# SuniderPra.net
KiCad netlist of a schematic drawn in EAGLE
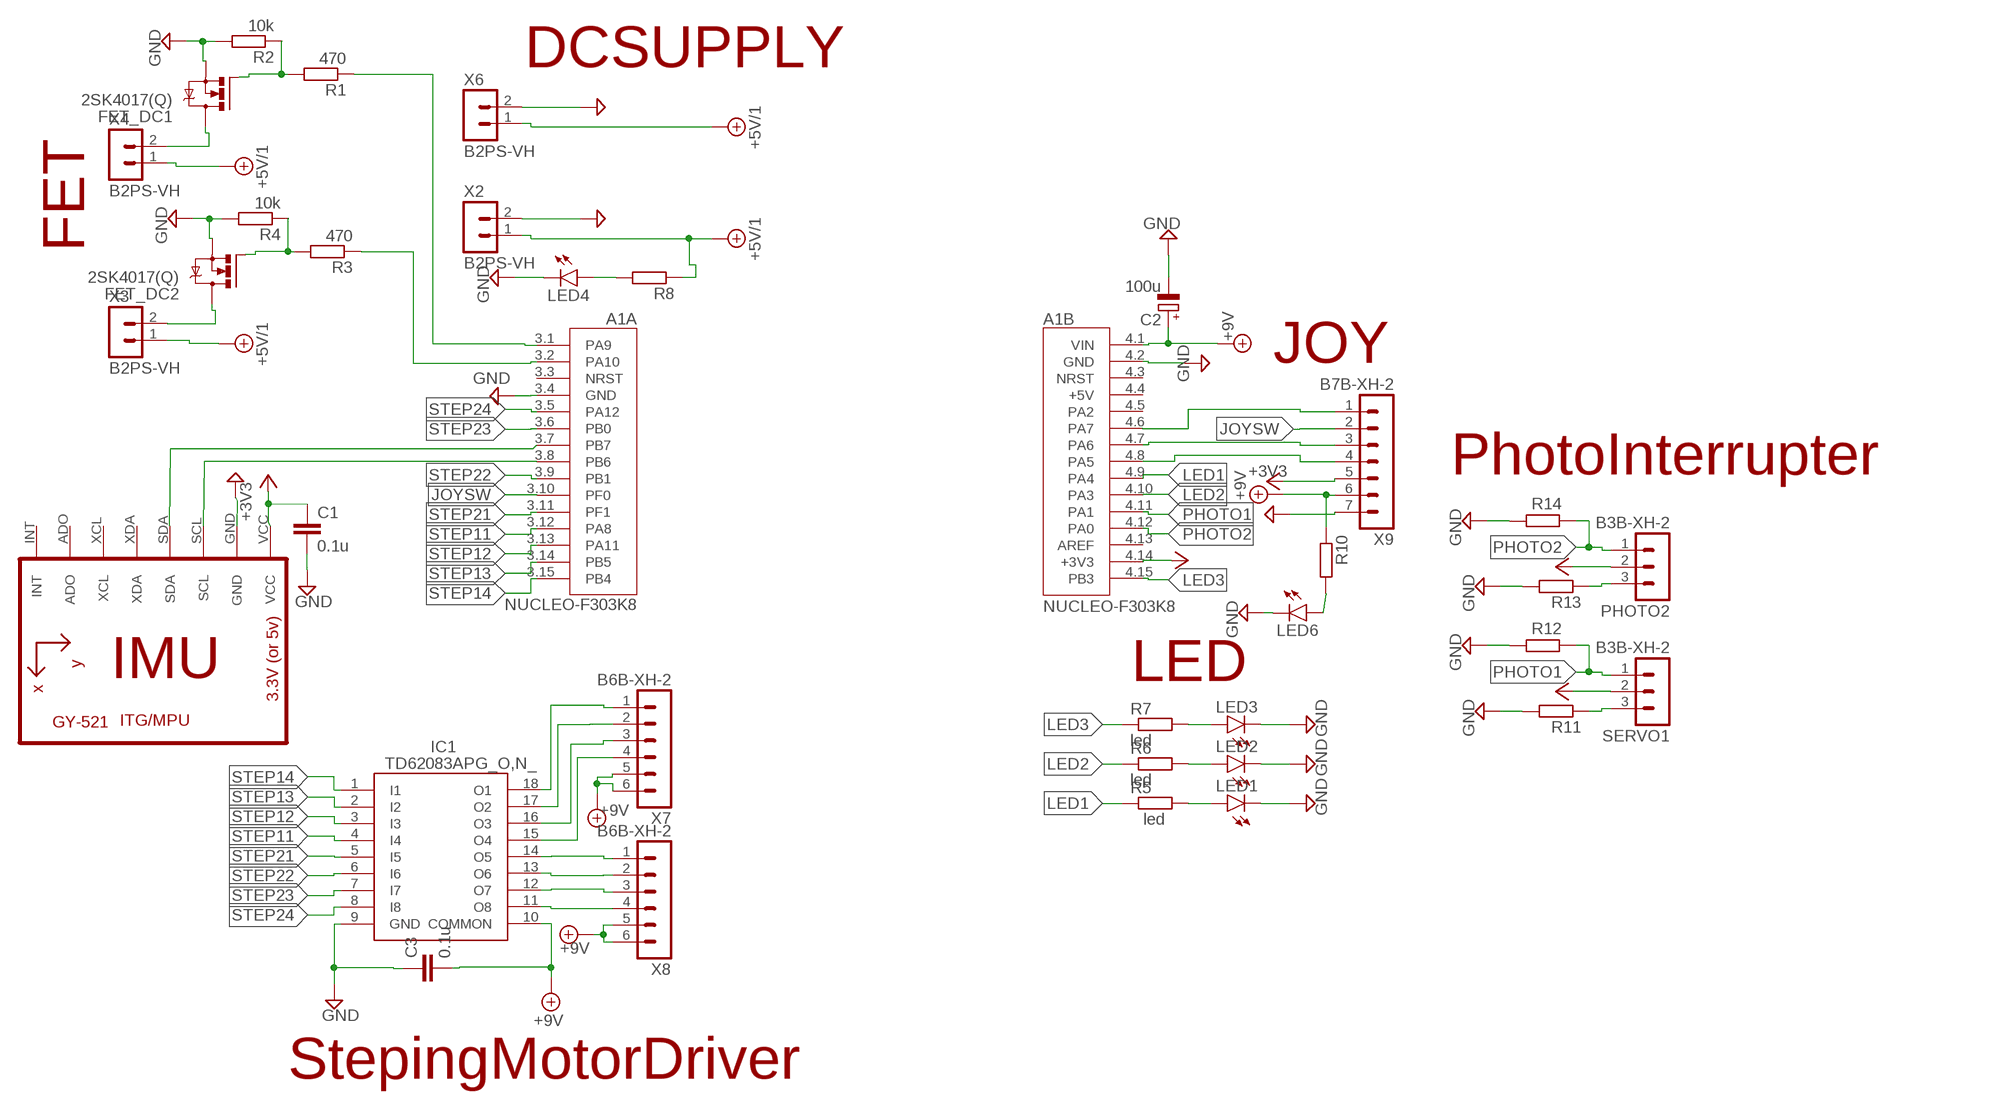
[diagram p0: schematic, sheet 1]

(export (version "E")
  (design (tool "Eeschema 10.0.6"))
  (components
    (comp (ref "A1")
      (value "NUCLEO-F303K8")
      (footprint "eagle-import:MODULE_NUCLEO-F303K8")
      (fields (field (name "MF") "STMicroelectronics"))
      (libsource (lib "eagle-import") (part "NUCLEO-F303K8"))
    )
    (comp (ref "C1")
      (value "0.1u")
      (footprint "eagle-import:C050-024X044")
      (libsource (lib "eagle-import") (part "C-EU050-024X044"))
    )
    (comp (ref "C2")
      (value "100u")
      (footprint "eagle-import:E2,5-6E")
      (libsource (lib "eagle-import") (part "CPOL-EUE2,5-6E"))
    )
    (comp (ref "C3")
      (value "0.1u")
      (footprint "eagle-import:C050-024X044")
      (libsource (lib "eagle-import") (part "C-EU050-024X044"))
    )
    (comp (ref "FET_DC1")
      (value "2SK4017(Q)")
      (footprint "eagle-import:TO230P230X650X740-3P")
      (fields (field (name "MF") "Toshiba Semiconductor"))
      (libsource (lib "eagle-import") (part "2SK4017(Q)"))
    )
    (comp (ref "FET_DC2")
      (value "2SK4017(Q)")
      (footprint "eagle-import:TO230P230X650X740-3P")
      (fields (field (name "MF") "Toshiba Semiconductor"))
      (libsource (lib "eagle-import") (part "2SK4017(Q)"))
    )
    (comp (ref "IC1")
      (value "TD62083APG_O,N_")
      (footprint "eagle-import:DIP762W60P254L2510H445Q18N")
      (fields
        (field (name "MANUFACTURER_PART_NUMBER") "TD62083APG(O,N)")
        (field (name "MOUSER_PART_NUMBER") "757-TD62083APGON")
      )
      (libsource (lib "eagle-import") (part "TD62083APG_O,N_"))
    )
    (comp (ref "IMU")
      (value "GY-521MPU6050")
      (footprint "eagle-import:GY-521")
      (libsource (lib "eagle-import") (part "GY-521MPU6050"))
    )
    (comp (ref "LED1")
      (value "LED3MM")
      (footprint "eagle-import:LED3MM")
      (libsource (lib "eagle-import") (part "LED3MM"))
    )
    (comp (ref "LED2")
      (value "LED3MM")
      (footprint "eagle-import:LED3MM")
      (libsource (lib "eagle-import") (part "LED3MM"))
    )
    (comp (ref "LED3")
      (value "LED3MM")
      (footprint "eagle-import:LED3MM")
      (libsource (lib "eagle-import") (part "LED3MM"))
    )
    (comp (ref "LED4")
      (value "LED3MM")
      (footprint "eagle-import:LED3MM")
      (libsource (lib "eagle-import") (part "LED3MM"))
    )
    (comp (ref "LED6")
      (value "LED3MM")
      (footprint "eagle-import:LED3MM")
      (libsource (lib "eagle-import") (part "LED3MM"))
    )
    (comp (ref "PHOTO2")
      (value "B3B-XH-2")
      (footprint "eagle-import:B3B-XH-A")
      (libsource (lib "eagle-import") (part "B3B-XH-2"))
    )
    (comp (ref "R1")
      (value "470")
      (footprint "eagle-import:0207_7")
      (libsource (lib "eagle-import") (part "R-EU_0207/7"))
    )
    (comp (ref "R2")
      (value "10k")
      (footprint "eagle-import:0207_7")
      (libsource (lib "eagle-import") (part "R-EU_0207/7"))
    )
    (comp (ref "R3")
      (value "470")
      (footprint "eagle-import:0207_7")
      (libsource (lib "eagle-import") (part "R-EU_0207/7"))
    )
    (comp (ref "R4")
      (value "10k")
      (footprint "eagle-import:0207_7")
      (libsource (lib "eagle-import") (part "R-EU_0207/7"))
    )
    (comp (ref "R5")
      (value "led")
      (footprint "eagle-import:0207_7")
      (libsource (lib "eagle-import") (part "R-EU_0207/7"))
    )
    (comp (ref "R6")
      (value "led")
      (footprint "eagle-import:0207_7")
      (libsource (lib "eagle-import") (part "R-EU_0207/7"))
    )
    (comp (ref "R7")
      (value "led")
      (footprint "eagle-import:0207_7")
      (libsource (lib "eagle-import") (part "R-EU_0207/7"))
    )
    (comp (ref "R8")
      (value "led")
      (footprint "eagle-import:0207_7")
      (libsource (lib "eagle-import") (part "R-EU_0207/7"))
    )
    (comp (ref "R10")
      (value "led")
      (footprint "eagle-import:0207_7")
      (libsource (lib "eagle-import") (part "R-EU_0207/7"))
    )
    (comp (ref "R11")
      (value "220")
      (footprint "eagle-import:0207_7")
      (libsource (lib "eagle-import") (part "R-EU_0207/7"))
    )
    (comp (ref "R12")
      (value "10k")
      (footprint "eagle-import:0207_7")
      (libsource (lib "eagle-import") (part "R-EU_0207/7"))
    )
    (comp (ref "R13")
      (value "220")
      (footprint "eagle-import:0207_7")
      (libsource (lib "eagle-import") (part "R-EU_0207/7"))
    )
    (comp (ref "R14")
      (value "10k")
      (footprint "eagle-import:0207_7")
      (libsource (lib "eagle-import") (part "R-EU_0207/7"))
    )
    (comp (ref "SERVO1")
      (value "B3B-XH-2")
      (footprint "eagle-import:B3B-XH-A")
      (libsource (lib "eagle-import") (part "B3B-XH-2"))
    )
    (comp (ref "X2")
      (value "B2PS-VH")
      (footprint "eagle-import:B2PS-VH")
      (libsource (lib "eagle-import") (part "B2PS-VH"))
    )
    (comp (ref "X3")
      (value "B2PS-VH")
      (footprint "eagle-import:B2PS-VH")
      (libsource (lib "eagle-import") (part "B2PS-VH"))
    )
    (comp (ref "X4")
      (value "B2PS-VH")
      (footprint "eagle-import:B2PS-VH")
      (libsource (lib "eagle-import") (part "B2PS-VH"))
    )
    (comp (ref "X6")
      (value "B2PS-VH")
      (footprint "eagle-import:B2PS-VH")
      (libsource (lib "eagle-import") (part "B2PS-VH"))
    )
    (comp (ref "X7")
      (value "B6B-XH-2")
      (footprint "eagle-import:B6B-XH-A")
      (libsource (lib "eagle-import") (part "B6B-XH-2"))
    )
    (comp (ref "X8")
      (value "B6B-XH-2")
      (footprint "eagle-import:B6B-XH-A")
      (libsource (lib "eagle-import") (part "B6B-XH-2"))
    )
    (comp (ref "X9")
      (value "B7B-XH-2")
      (footprint "eagle-import:B7B-XH-A")
      (libsource (lib "eagle-import") (part "B7B-XH-2"))
    )
  )
  (nets
    (net (code "1") (name "+3V3") (class "Default")
      (node (ref "A1") (pin "4.14") (pinfunction "+3V3_4.14") (pintype "bidirectional"))
      (node (ref "C1") (pin "1") (pinfunction "1_1") (pintype "passive"))
      (node (ref "IMU") (pin "VCC") (pinfunction "VCC_VCC") (pintype "bidirectional"))
      (node (ref "PHOTO2") (pin "2") (pinfunction "2_2") (pintype "passive"))
      (node (ref "SERVO1") (pin "2") (pinfunction "2_2") (pintype "passive"))
      (node (ref "X9") (pin "5") (pinfunction "5_5") (pintype "passive"))
    )
    (net (code "2") (name "+5V{slash}1") (class "Default")
      (node (ref "R8") (pin "1") (pinfunction "1_1") (pintype "passive"))
      (node (ref "X2") (pin "1") (pinfunction "1_1") (pintype "passive"))
      (node (ref "X3") (pin "1") (pinfunction "1_1") (pintype "passive"))
      (node (ref "X4") (pin "1") (pinfunction "1_1") (pintype "passive"))
      (node (ref "X6") (pin "1") (pinfunction "1_1") (pintype "passive"))
    )
    (net (code "3") (name "+9V") (class "Default")
      (node (ref "A1") (pin "4.1") (pinfunction "VIN_4.1") (pintype "bidirectional"))
      (node (ref "C2") (pin "+") (pinfunction "+_+") (pintype "passive"))
      (node (ref "C3") (pin "2") (pinfunction "2_2") (pintype "passive"))
      (node (ref "IC1") (pin "10") (pinfunction "COMMON_10") (pintype "bidirectional"))
      (node (ref "R10") (pin "1") (pinfunction "1_1") (pintype "passive"))
      (node (ref "X7") (pin "5") (pinfunction "5_5") (pintype "passive"))
      (node (ref "X7") (pin "6") (pinfunction "6_6") (pintype "passive"))
      (node (ref "X8") (pin "5") (pinfunction "5_5") (pintype "passive"))
      (node (ref "X8") (pin "6") (pinfunction "6_6") (pintype "passive"))
      (node (ref "X9") (pin "6") (pinfunction "6_6") (pintype "passive"))
    )
    (net (code "4") (name "GND") (class "Default")
      (node (ref "A1") (pin "3.4") (pinfunction "GND_3.4") (pintype "bidirectional"))
      (node (ref "A1") (pin "4.2") (pinfunction "GND_4.2") (pintype "bidirectional"))
      (node (ref "C1") (pin "2") (pinfunction "2_2") (pintype "passive"))
      (node (ref "C2") (pin "-") (pinfunction "-_-") (pintype "passive"))
      (node (ref "C3") (pin "1") (pinfunction "1_1") (pintype "passive"))
      (node (ref "FET_DC1") (pin "3") (pinfunction "S_3") (pintype "passive"))
      (node (ref "FET_DC2") (pin "3") (pinfunction "S_3") (pintype "passive"))
      (node (ref "IC1") (pin "9") (pinfunction "GND_9") (pintype "bidirectional"))
      (node (ref "IMU") (pin "GND") (pinfunction "GND_GND") (pintype "bidirectional"))
      (node (ref "LED1") (pin "K") (pinfunction "C_K") (pintype "passive"))
      (node (ref "LED2") (pin "K") (pinfunction "C_K") (pintype "passive"))
      (node (ref "LED3") (pin "K") (pinfunction "C_K") (pintype "passive"))
      (node (ref "LED4") (pin "K") (pinfunction "C_K") (pintype "passive"))
      (node (ref "LED6") (pin "K") (pinfunction "C_K") (pintype "passive"))
      (node (ref "R11") (pin "2") (pinfunction "2_2") (pintype "passive"))
      (node (ref "R12") (pin "2") (pinfunction "2_2") (pintype "passive"))
      (node (ref "R13") (pin "2") (pinfunction "2_2") (pintype "passive"))
      (node (ref "R14") (pin "2") (pinfunction "2_2") (pintype "passive"))
      (node (ref "R2") (pin "2") (pinfunction "2_2") (pintype "passive"))
      (node (ref "R4") (pin "2") (pinfunction "2_2") (pintype "passive"))
      (node (ref "X2") (pin "2") (pinfunction "2_2") (pintype "passive"))
      (node (ref "X6") (pin "2") (pinfunction "2_2") (pintype "passive"))
      (node (ref "X9") (pin "7") (pinfunction "7_7") (pintype "passive"))
    )
    (net (code "5") (name "JOYSW") (class "Default")
      (node (ref "A1") (pin "3.10") (pinfunction "PF0_3.10") (pintype "bidirectional"))
      (node (ref "X9") (pin "2") (pinfunction "2_2") (pintype "passive"))
    )
    (net (code "6") (name "LED1") (class "Default")
      (node (ref "A1") (pin "4.9") (pinfunction "PA4_4.9") (pintype "bidirectional"))
      (node (ref "R5") (pin "1") (pinfunction "1_1") (pintype "passive"))
    )
    (net (code "7") (name "LED2") (class "Default")
      (node (ref "A1") (pin "4.10") (pinfunction "PA3_4.10") (pintype "bidirectional"))
      (node (ref "R6") (pin "1") (pinfunction "1_1") (pintype "passive"))
    )
    (net (code "8") (name "LED3") (class "Default")
      (node (ref "A1") (pin "4.15") (pinfunction "PB3_4.15") (pintype "bidirectional"))
      (node (ref "R7") (pin "1") (pinfunction "1_1") (pintype "passive"))
    )
    (net (code "9") (name "Net-(A1A-PA9)") (class "Default")
      (node (ref "A1") (pin "3.1") (pinfunction "PA9_3.1") (pintype "bidirectional"))
      (node (ref "R1") (pin "1") (pinfunction "1_1") (pintype "passive"))
    )
    (net (code "10") (name "Net-(A1A-PA10)") (class "Default")
      (node (ref "A1") (pin "3.2") (pinfunction "PA10_3.2") (pintype "bidirectional"))
      (node (ref "R3") (pin "1") (pinfunction "1_1") (pintype "passive"))
    )
    (net (code "11") (name "Net-(A1A-PB6)") (class "Default")
      (node (ref "A1") (pin "3.8") (pinfunction "PB6_3.8") (pintype "bidirectional"))
      (node (ref "IMU") (pin "SCL") (pinfunction "SCL_SCL") (pintype "bidirectional"))
    )
    (net (code "12") (name "Net-(A1A-PB7)") (class "Default")
      (node (ref "A1") (pin "3.7") (pinfunction "PB7_3.7") (pintype "bidirectional"))
      (node (ref "IMU") (pin "SDA") (pinfunction "SDA_SDA") (pintype "bidirectional"))
    )
    (net (code "13") (name "Net-(A1B-PA5)") (class "Default")
      (node (ref "A1") (pin "4.8") (pinfunction "PA5_4.8") (pintype "bidirectional"))
      (node (ref "X9") (pin "4") (pinfunction "4_4") (pintype "passive"))
    )
    (net (code "14") (name "Net-(A1B-PA6)") (class "Default")
      (node (ref "A1") (pin "4.7") (pinfunction "PA6_4.7") (pintype "bidirectional"))
      (node (ref "X9") (pin "3") (pinfunction "3_3") (pintype "passive"))
    )
    (net (code "15") (name "Net-(A1B-PA7)") (class "Default")
      (node (ref "A1") (pin "4.6") (pinfunction "PA7_4.6") (pintype "bidirectional"))
      (node (ref "X9") (pin "1") (pinfunction "1_1") (pintype "passive"))
    )
    (net (code "16") (name "Net-(FET_DC1-D)") (class "Default")
      (node (ref "FET_DC1") (pin "2") (pinfunction "D_2") (pintype "passive"))
      (node (ref "X4") (pin "2") (pinfunction "2_2") (pintype "passive"))
    )
    (net (code "17") (name "Net-(FET_DC1-G)") (class "Default")
      (node (ref "FET_DC1") (pin "1") (pinfunction "G_1") (pintype "passive"))
      (node (ref "R1") (pin "2") (pinfunction "2_2") (pintype "passive"))
      (node (ref "R2") (pin "1") (pinfunction "1_1") (pintype "passive"))
    )
    (net (code "18") (name "Net-(FET_DC2-D)") (class "Default")
      (node (ref "FET_DC2") (pin "2") (pinfunction "D_2") (pintype "passive"))
      (node (ref "X3") (pin "2") (pinfunction "2_2") (pintype "passive"))
    )
    (net (code "19") (name "Net-(FET_DC2-G)") (class "Default")
      (node (ref "FET_DC2") (pin "1") (pinfunction "G_1") (pintype "passive"))
      (node (ref "R3") (pin "2") (pinfunction "2_2") (pintype "passive"))
      (node (ref "R4") (pin "1") (pinfunction "1_1") (pintype "passive"))
    )
    (net (code "20") (name "Net-(IC1-O1)") (class "Default")
      (node (ref "IC1") (pin "18") (pinfunction "O1_18") (pintype "bidirectional"))
      (node (ref "X7") (pin "1") (pinfunction "1_1") (pintype "passive"))
    )
    (net (code "21") (name "Net-(IC1-O2)") (class "Default")
      (node (ref "IC1") (pin "17") (pinfunction "O2_17") (pintype "bidirectional"))
      (node (ref "X7") (pin "2") (pinfunction "2_2") (pintype "passive"))
    )
    (net (code "22") (name "Net-(IC1-O3)") (class "Default")
      (node (ref "IC1") (pin "16") (pinfunction "O3_16") (pintype "bidirectional"))
      (node (ref "X7") (pin "3") (pinfunction "3_3") (pintype "passive"))
    )
    (net (code "23") (name "Net-(IC1-O4)") (class "Default")
      (node (ref "IC1") (pin "15") (pinfunction "O4_15") (pintype "bidirectional"))
      (node (ref "X7") (pin "4") (pinfunction "4_4") (pintype "passive"))
    )
    (net (code "24") (name "Net-(IC1-O5)") (class "Default")
      (node (ref "IC1") (pin "14") (pinfunction "O5_14") (pintype "bidirectional"))
      (node (ref "X8") (pin "1") (pinfunction "1_1") (pintype "passive"))
    )
    (net (code "25") (name "Net-(IC1-O6)") (class "Default")
      (node (ref "IC1") (pin "13") (pinfunction "O6_13") (pintype "bidirectional"))
      (node (ref "X8") (pin "2") (pinfunction "2_2") (pintype "passive"))
    )
    (net (code "26") (name "Net-(IC1-O7)") (class "Default")
      (node (ref "IC1") (pin "12") (pinfunction "O7_12") (pintype "bidirectional"))
      (node (ref "X8") (pin "3") (pinfunction "3_3") (pintype "passive"))
    )
    (net (code "27") (name "Net-(IC1-O8)") (class "Default")
      (node (ref "IC1") (pin "11") (pinfunction "O8_11") (pintype "bidirectional"))
      (node (ref "X8") (pin "4") (pinfunction "4_4") (pintype "passive"))
    )
    (net (code "28") (name "Net-(LED1-PadA)") (class "Default")
      (node (ref "LED1") (pin "A") (pinfunction "A_A") (pintype "passive"))
      (node (ref "R5") (pin "2") (pinfunction "2_2") (pintype "passive"))
    )
    (net (code "29") (name "Net-(LED2-PadA)") (class "Default")
      (node (ref "LED2") (pin "A") (pinfunction "A_A") (pintype "passive"))
      (node (ref "R6") (pin "2") (pinfunction "2_2") (pintype "passive"))
    )
    (net (code "30") (name "Net-(LED3-PadA)") (class "Default")
      (node (ref "LED3") (pin "A") (pinfunction "A_A") (pintype "passive"))
      (node (ref "R7") (pin "2") (pinfunction "2_2") (pintype "passive"))
    )
    (net (code "31") (name "Net-(LED4-PadA)") (class "Default")
      (node (ref "LED4") (pin "A") (pinfunction "A_A") (pintype "passive"))
      (node (ref "R8") (pin "2") (pinfunction "2_2") (pintype "passive"))
    )
    (net (code "32") (name "Net-(LED6-PadA)") (class "Default")
      (node (ref "LED6") (pin "A") (pinfunction "A_A") (pintype "passive"))
      (node (ref "R10") (pin "2") (pinfunction "2_2") (pintype "passive"))
    )
    (net (code "33") (name "Net-(PHOTO2-Pad3)") (class "Default")
      (node (ref "PHOTO2") (pin "3") (pinfunction "3_3") (pintype "passive"))
      (node (ref "R13") (pin "1") (pinfunction "1_1") (pintype "passive"))
    )
    (net (code "34") (name "Net-(R11-Pad1)") (class "Default")
      (node (ref "R11") (pin "1") (pinfunction "1_1") (pintype "passive"))
      (node (ref "SERVO1") (pin "3") (pinfunction "3_3") (pintype "passive"))
    )
    (net (code "35") (name "PHOTO1") (class "Default")
      (node (ref "A1") (pin "4.11") (pinfunction "PA1_4.11") (pintype "bidirectional"))
      (node (ref "R12") (pin "1") (pinfunction "1_1") (pintype "passive"))
      (node (ref "SERVO1") (pin "1") (pinfunction "1_1") (pintype "passive"))
    )
    (net (code "36") (name "PHOTO2") (class "Default")
      (node (ref "A1") (pin "4.12") (pinfunction "PA0_4.12") (pintype "bidirectional"))
      (node (ref "PHOTO2") (pin "1") (pinfunction "1_1") (pintype "passive"))
      (node (ref "R14") (pin "1") (pinfunction "1_1") (pintype "passive"))
    )
    (net (code "37") (name "STEP11") (class "Default")
      (node (ref "A1") (pin "3.12") (pinfunction "PA8_3.12") (pintype "bidirectional"))
      (node (ref "IC1") (pin "4") (pinfunction "I4_4") (pintype "bidirectional"))
    )
    (net (code "38") (name "STEP12") (class "Default")
      (node (ref "A1") (pin "3.13") (pinfunction "PA11_3.13") (pintype "bidirectional"))
      (node (ref "IC1") (pin "3") (pinfunction "I3_3") (pintype "bidirectional"))
    )
    (net (code "39") (name "STEP13") (class "Default")
      (node (ref "A1") (pin "3.14") (pinfunction "PB5_3.14") (pintype "bidirectional"))
      (node (ref "IC1") (pin "2") (pinfunction "I2_2") (pintype "bidirectional"))
    )
    (net (code "40") (name "STEP14") (class "Default")
      (node (ref "A1") (pin "3.15") (pinfunction "PB4_3.15") (pintype "bidirectional"))
      (node (ref "IC1") (pin "1") (pinfunction "I1_1") (pintype "bidirectional"))
    )
    (net (code "41") (name "STEP21") (class "Default")
      (node (ref "A1") (pin "3.11") (pinfunction "PF1_3.11") (pintype "bidirectional"))
      (node (ref "IC1") (pin "5") (pinfunction "I5_5") (pintype "bidirectional"))
    )
    (net (code "42") (name "STEP22") (class "Default")
      (node (ref "A1") (pin "3.9") (pinfunction "PB1_3.9") (pintype "bidirectional"))
      (node (ref "IC1") (pin "6") (pinfunction "I6_6") (pintype "bidirectional"))
    )
    (net (code "43") (name "STEP23") (class "Default")
      (node (ref "A1") (pin "3.6") (pinfunction "PB0_3.6") (pintype "bidirectional"))
      (node (ref "IC1") (pin "7") (pinfunction "I7_7") (pintype "bidirectional"))
    )
    (net (code "44") (name "STEP24") (class "Default")
      (node (ref "A1") (pin "3.5") (pinfunction "PA12_3.5") (pintype "bidirectional"))
      (node (ref "IC1") (pin "8") (pinfunction "I8_8") (pintype "bidirectional"))
    )
    (net (code "45") (name "unconnected-(A1A-NRST-Pad3.3)") (class "Default")
      (node (ref "A1") (pin "3.3") (pinfunction "NRST_3.3") (pintype "bidirectional"))
    )
    (net (code "46") (name "unconnected-(A1B-+5V-Pad4.4)") (class "Default")
      (node (ref "A1") (pin "4.4") (pinfunction "+5V_4.4") (pintype "bidirectional"))
    )
    (net (code "47") (name "unconnected-(A1B-AREF-Pad4.13)") (class "Default")
      (node (ref "A1") (pin "4.13") (pinfunction "AREF_4.13") (pintype "bidirectional"))
    )
    (net (code "48") (name "unconnected-(A1B-NRST-Pad4.3)") (class "Default")
      (node (ref "A1") (pin "4.3") (pinfunction "NRST_4.3") (pintype "bidirectional"))
    )
    (net (code "49") (name "unconnected-(A1B-PA2-Pad4.5)") (class "Default")
      (node (ref "A1") (pin "4.5") (pinfunction "PA2_4.5") (pintype "bidirectional"))
    )
    (net (code "50") (name "unconnected-(IMU-PadADO)") (class "Default")
      (node (ref "IMU") (pin "ADO") (pinfunction "ADO_ADO") (pintype "bidirectional"))
    )
    (net (code "51") (name "unconnected-(IMU-PadINT)") (class "Default")
      (node (ref "IMU") (pin "INT") (pinfunction "INT_INT") (pintype "bidirectional"))
    )
    (net (code "52") (name "unconnected-(IMU-PadXCL)") (class "Default")
      (node (ref "IMU") (pin "XCL") (pinfunction "XCL_XCL") (pintype "bidirectional"))
    )
    (net (code "53") (name "unconnected-(IMU-PadXDA)") (class "Default")
      (node (ref "IMU") (pin "XDA") (pinfunction "XDA_XDA") (pintype "bidirectional"))
    )
  )
)
